# ColorDetector.net
KiCad netlist of a schematic drawn in EAGLE
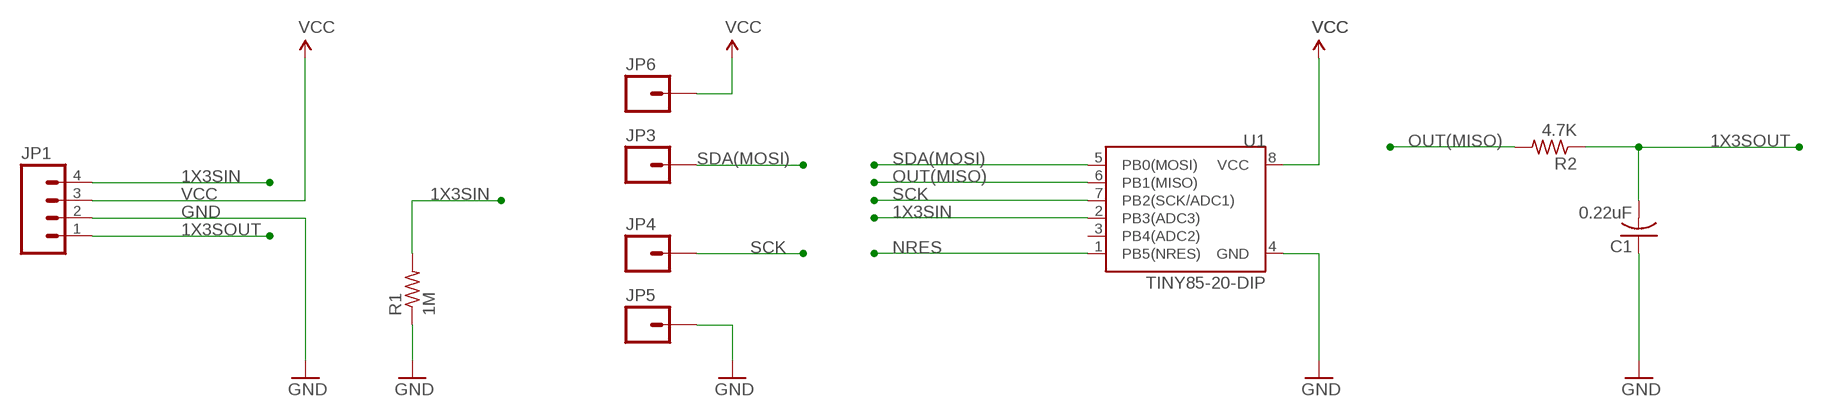
[diagram p0: schematic, sheet 1]

(export (version "E")
  (design (tool "Eeschema 10.0.6"))
  (components
    (comp (ref "C1")
      (value "0.22uF")
      (footprint "eagle-import:C0402")
      (libsource (lib "eagle-import") (part "C-USC0402"))
    )
    (comp (ref "JP1")
      (value "M04PTH")
      (footprint "eagle-import:1X04")
      (libsource (lib "eagle-import") (part "M04PTH"))
    )
    (comp (ref "JP3")
      (value "M01PTH")
      (footprint "eagle-import:1X01")
      (libsource (lib "eagle-import") (part "M01PTH"))
    )
    (comp (ref "JP4")
      (value "M01PTH")
      (footprint "eagle-import:1X01")
      (libsource (lib "eagle-import") (part "M01PTH"))
    )
    (comp (ref "JP5")
      (value "M01PTH")
      (footprint "eagle-import:1X01")
      (libsource (lib "eagle-import") (part "M01PTH"))
    )
    (comp (ref "JP6")
      (value "M01PTH")
      (footprint "eagle-import:1X01")
      (libsource (lib "eagle-import") (part "M01PTH"))
    )
    (comp (ref "R1")
      (value "1M")
      (footprint "eagle-import:R0603")
      (libsource (lib "eagle-import") (part "R-US_R0603"))
    )
    (comp (ref "R2")
      (value "4.7K")
      (footprint "eagle-import:R0603")
      (libsource (lib "eagle-import") (part "R-US_R0603"))
    )
    (comp (ref "U1")
      (value "TINY85-20-DIP")
      (footprint "eagle-import:DIP08")
      (libsource (lib "eagle-import") (part "ATTINY45TINY85-20-DIP"))
    )
  )
  (nets
    (net (code "1") (name "/1X3SIN") (class "Default")
      (node (ref "JP1") (pin "4") (pinfunction "4_4") (pintype "passive"))
      (node (ref "R1") (pin "2") (pinfunction "2_2") (pintype "passive"))
      (node (ref "U1") (pin "2") (pinfunction "PB3(ADC3)_2") (pintype "bidirectional"))
    )
    (net (code "2") (name "/1X3SOUT") (class "Default")
      (node (ref "C1") (pin "2") (pinfunction "2_2") (pintype "passive"))
      (node (ref "JP1") (pin "1") (pinfunction "1_1") (pintype "passive"))
      (node (ref "R2") (pin "1") (pinfunction "1_1") (pintype "passive"))
    )
    (net (code "3") (name "/NRES") (class "Default")
      (node (ref "U1") (pin "1") (pinfunction "PB5(NRES)_1") (pintype "bidirectional"))
    )
    (net (code "4") (name "/OUT(MISO)") (class "Default")
      (node (ref "R2") (pin "2") (pinfunction "2_2") (pintype "passive"))
      (node (ref "U1") (pin "6") (pinfunction "PB1(MISO)_6") (pintype "bidirectional"))
    )
    (net (code "5") (name "/SCK") (class "Default")
      (node (ref "JP4") (pin "1") (pinfunction "1_1") (pintype "passive"))
      (node (ref "U1") (pin "7") (pinfunction "PB2(SCK/ADC1)_7") (pintype "bidirectional"))
    )
    (net (code "6") (name "/SDA(MOSI)") (class "Default")
      (node (ref "JP3") (pin "1") (pinfunction "1_1") (pintype "passive"))
      (node (ref "U1") (pin "5") (pinfunction "PB0(MOSI)_5") (pintype "bidirectional"))
    )
    (net (code "7") (name "GND") (class "Default")
      (node (ref "C1") (pin "1") (pinfunction "1_1") (pintype "passive"))
      (node (ref "JP1") (pin "2") (pinfunction "2_2") (pintype "passive"))
      (node (ref "JP5") (pin "1") (pinfunction "1_1") (pintype "passive"))
      (node (ref "R1") (pin "1") (pinfunction "1_1") (pintype "passive"))
      (node (ref "U1") (pin "4") (pinfunction "GND_4") (pintype "bidirectional"))
    )
    (net (code "8") (name "VCC") (class "Default")
      (node (ref "JP1") (pin "3") (pinfunction "3_3") (pintype "passive"))
      (node (ref "JP6") (pin "1") (pinfunction "1_1") (pintype "passive"))
      (node (ref "U1") (pin "8") (pinfunction "VCC_8") (pintype "bidirectional"))
    )
    (net (code "9") (name "unconnected-(U1-PB4(ADC2)-Pad3)") (class "Default")
      (node (ref "U1") (pin "3") (pinfunction "PB4(ADC2)_3") (pintype "bidirectional"))
    )
  )
)
